# smartbbq.net
KiCad netlist of a schematic drawn in EAGLE
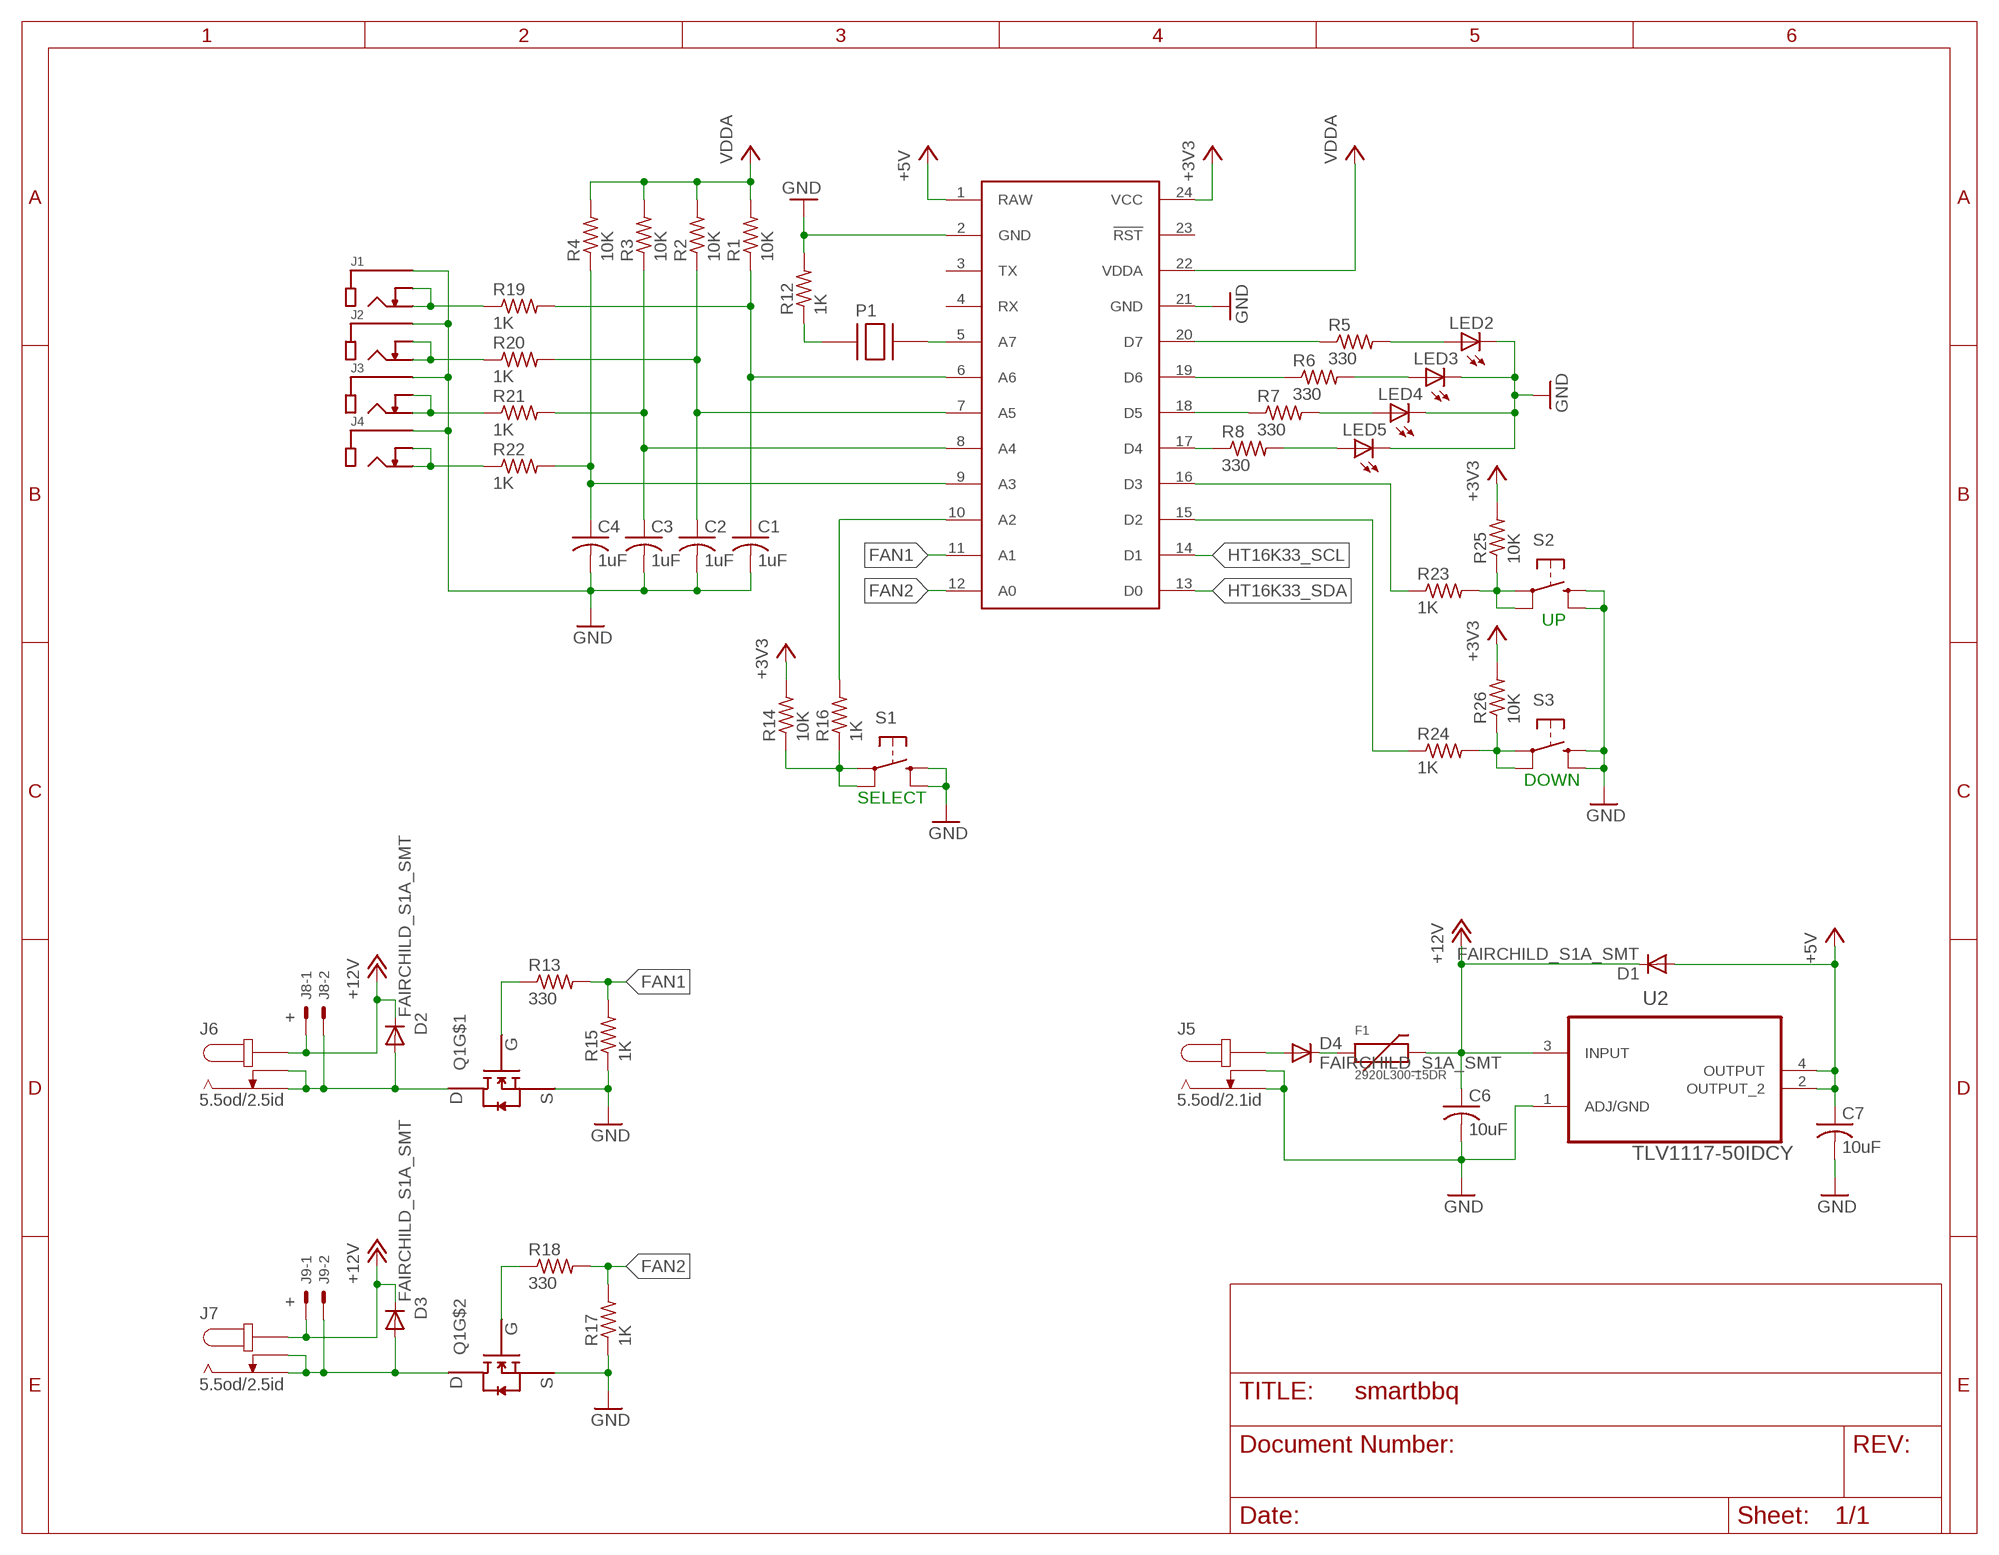
[diagram p0: schematic, sheet 1, part 1 of 2]
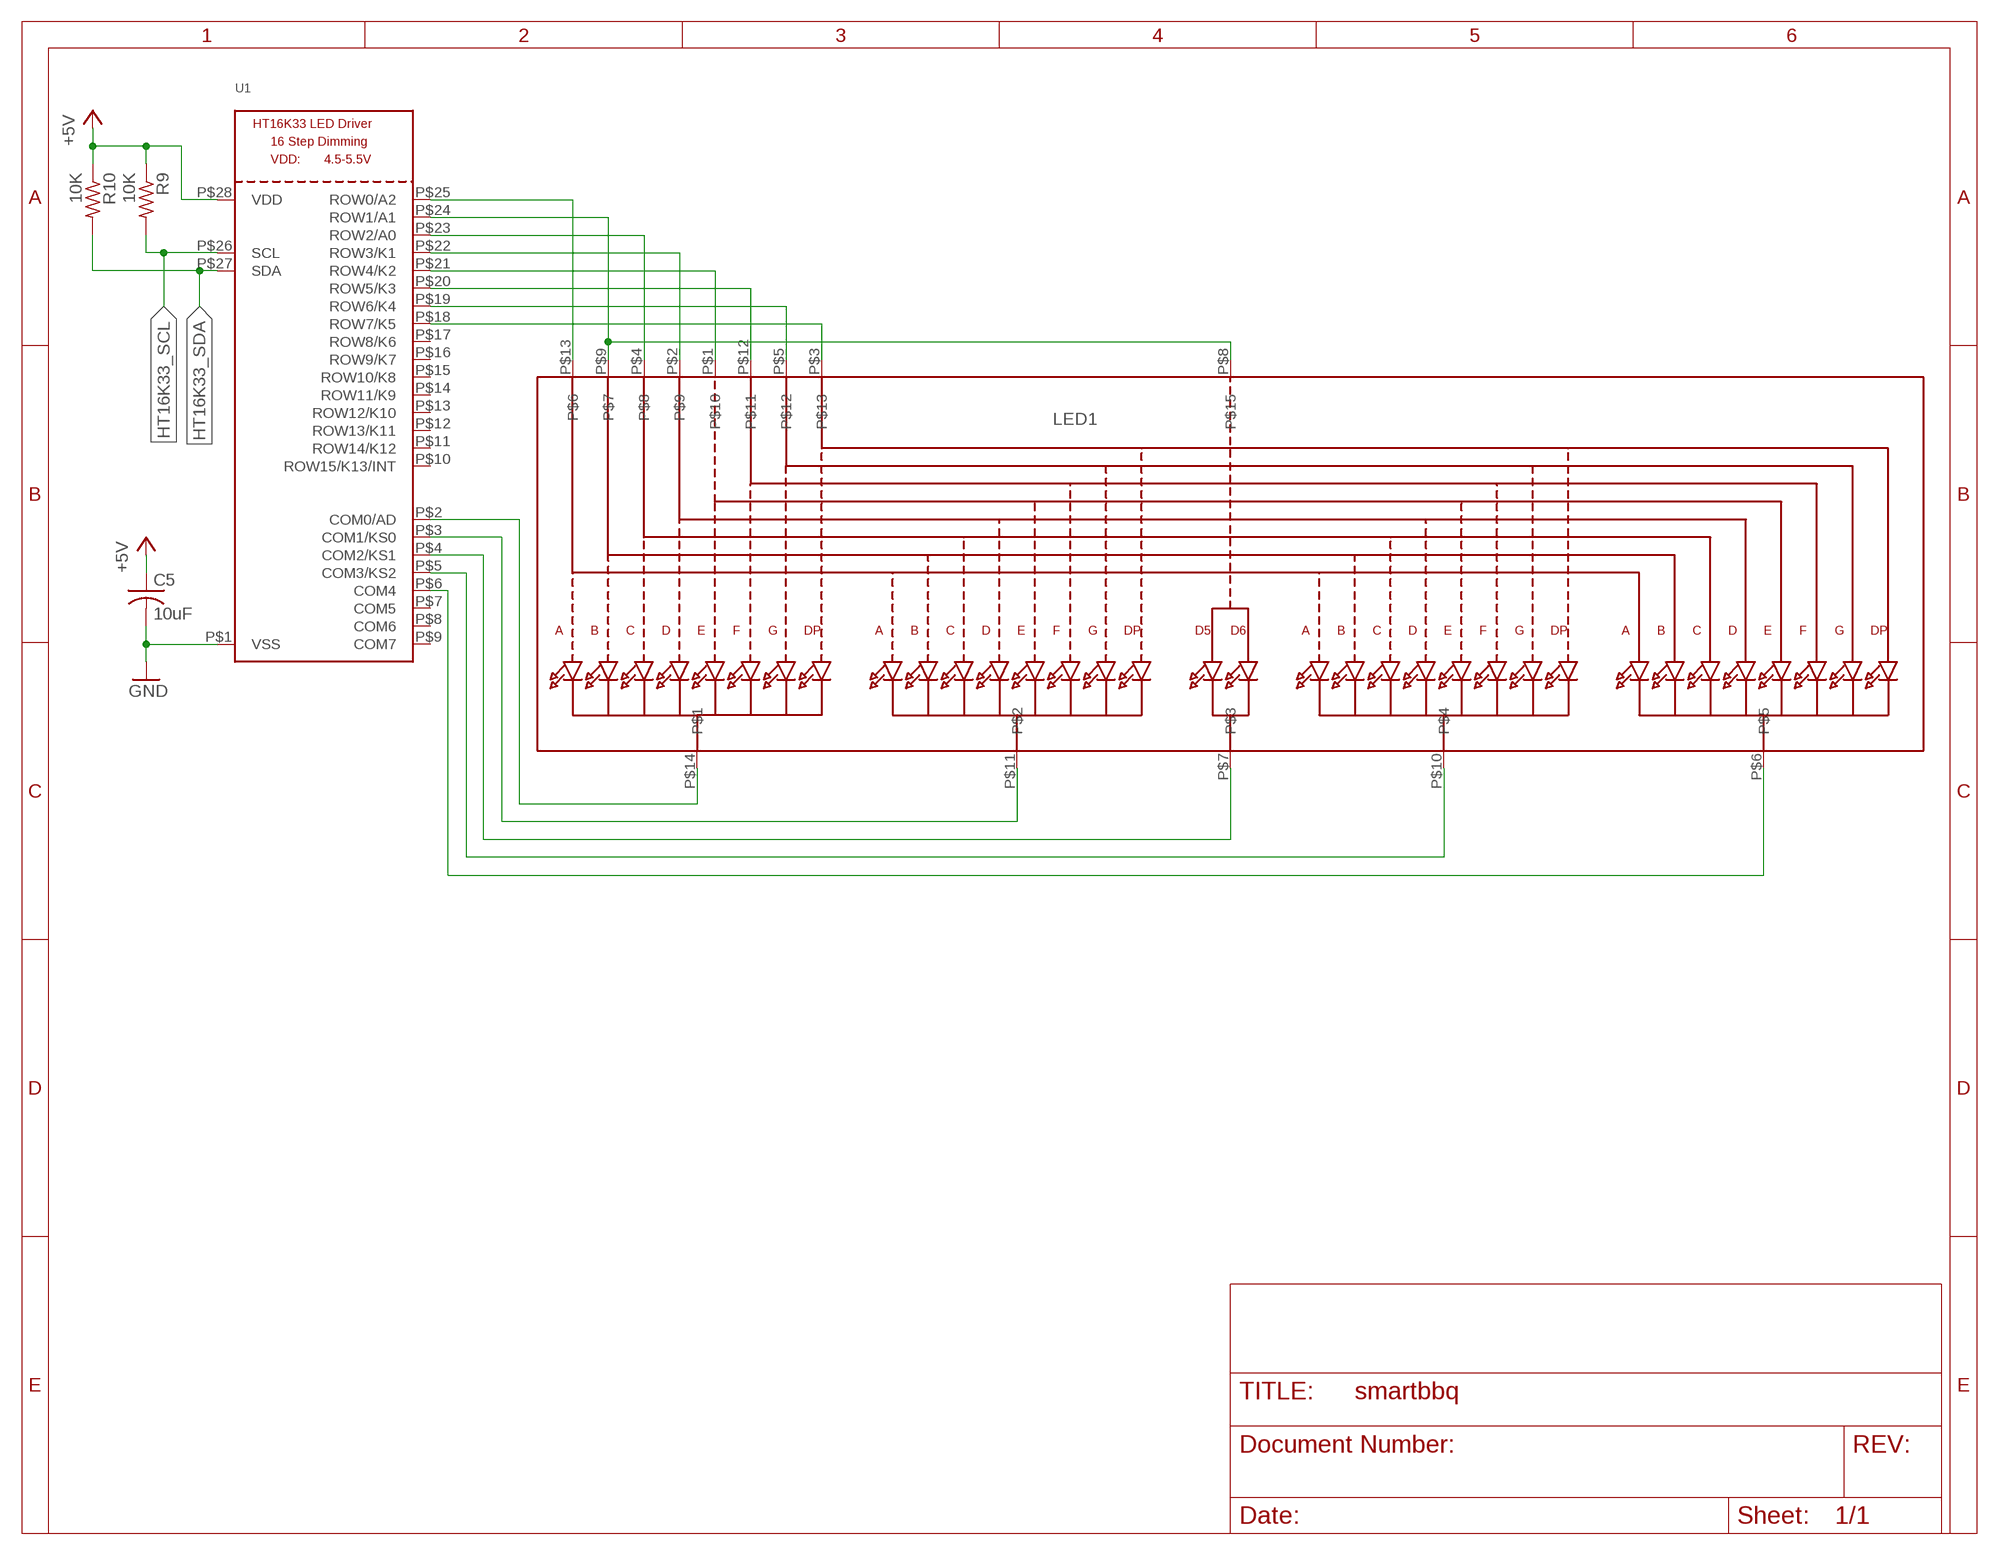
[diagram p1: schematic, sheet 1, part 2 of 2]

(export (version "E")
  (design (tool "Eeschema 10.0.6"))
  (components
    (comp (ref "C1")
      (value "1uF")
      (footprint "eagle-import:C0805")
      (libsource (lib "eagle-import") (part "C-USC0805"))
    )
    (comp (ref "C2")
      (value "1uF")
      (footprint "eagle-import:C0805")
      (libsource (lib "eagle-import") (part "C-USC0805"))
    )
    (comp (ref "C3")
      (value "1uF")
      (footprint "eagle-import:C0805")
      (libsource (lib "eagle-import") (part "C-USC0805"))
    )
    (comp (ref "C4")
      (value "1uF")
      (footprint "eagle-import:C0805")
      (libsource (lib "eagle-import") (part "C-USC0805"))
    )
    (comp (ref "C5")
      (value "10uF")
      (footprint "eagle-import:C0805")
      (libsource (lib "eagle-import") (part "C-USC0805"))
    )
    (comp (ref "C6")
      (value "10uF")
      (footprint "eagle-import:C0805")
      (libsource (lib "eagle-import") (part "C-USC0805"))
    )
    (comp (ref "C7")
      (value "10uF")
      (footprint "eagle-import:C0805")
      (libsource (lib "eagle-import") (part "C-USC0805"))
    )
    (comp (ref "D1")
      (value "FAIRCHILD_S1A_SMT")
      (footprint "eagle-import:FAIRCHILD_S1A_SMT")
      (libsource (lib "eagle-import") (part "FAIRCHILD_S1A_SMT"))
    )
    (comp (ref "D2")
      (value "FAIRCHILD_S1A_SMT")
      (footprint "eagle-import:FAIRCHILD_S1A_SMT")
      (libsource (lib "eagle-import") (part "FAIRCHILD_S1A_SMT"))
    )
    (comp (ref "D3")
      (value "FAIRCHILD_S1A_SMT")
      (footprint "eagle-import:FAIRCHILD_S1A_SMT")
      (libsource (lib "eagle-import") (part "FAIRCHILD_S1A_SMT"))
    )
    (comp (ref "D4")
      (value "FAIRCHILD_S1A_SMT")
      (footprint "eagle-import:FAIRCHILD_S1A_SMT")
      (libsource (lib "eagle-import") (part "FAIRCHILD_S1A_SMT"))
    )
    (comp (ref "F1")
      (value "2920L300-15DR")
      (footprint "eagle-import:2920L300-15DR")
      (libsource (lib "eagle-import") (part "2920L300-15DR"))
    )
    (comp (ref "J1")
      (value "MJ_2523_SMT")
      (footprint "eagle-import:MJ_2523_SMT")
      (libsource (lib "eagle-import") (part "MJ_2523_SMT"))
    )
    (comp (ref "J2")
      (value "MJ_2523_SMT")
      (footprint "eagle-import:MJ_2523_SMT")
      (libsource (lib "eagle-import") (part "MJ_2523_SMT"))
    )
    (comp (ref "J3")
      (value "MJ_2523_SMT")
      (footprint "eagle-import:MJ_2523_SMT")
      (libsource (lib "eagle-import") (part "MJ_2523_SMT"))
    )
    (comp (ref "J4")
      (value "MJ_2523_SMT")
      (footprint "eagle-import:MJ_2523_SMT")
      (libsource (lib "eagle-import") (part "MJ_2523_SMT"))
    )
    (comp (ref "J5")
      (value "5.5od/2.1id")
      (footprint "eagle-import:PJ_002AH_SMT")
      (libsource (lib "eagle-import") (part "PJ_002AH_SMT"))
    )
    (comp (ref "J6")
      (value "5.5od/2.5id")
      (footprint "eagle-import:PJ_002AH_SMT")
      (libsource (lib "eagle-import") (part "PJ_002AH_SMT"))
    )
    (comp (ref "J7")
      (value "5.5od/2.5id")
      (footprint "eagle-import:PJ_002AH_SMT")
      (libsource (lib "eagle-import") (part "PJ_002AH_SMT"))
    )
    (comp (ref "J8")
      (value "+")
      (footprint "eagle-import:7395-02")
      (libsource (lib "eagle-import") (part "22-?-0205-7028"))
    )
    (comp (ref "J9")
      (value "+")
      (footprint "eagle-import:7395-02")
      (libsource (lib "eagle-import") (part "22-?-0205-7028"))
    )
    (comp (ref "LED1")
      (value "DISP_SEGMENT_4DIGIT_BL-Q56C43")
      (footprint "eagle-import:SEGMENT-BL-Q56C43")
      (libsource (lib "eagle-import") (part "DISP_SEGMENT_4DIGIT_BL-Q56C43"))
    )
    (comp (ref "LED2")
      (value "LEDCHIPLED_0805")
      (footprint "eagle-import:CHIPLED_0805")
      (libsource (lib "eagle-import") (part "LEDCHIPLED_0805"))
    )
    (comp (ref "LED3")
      (value "LEDCHIPLED_0805")
      (footprint "eagle-import:CHIPLED_0805")
      (libsource (lib "eagle-import") (part "LEDCHIPLED_0805"))
    )
    (comp (ref "LED4")
      (value "LEDCHIPLED_0805")
      (footprint "eagle-import:CHIPLED_0805")
      (libsource (lib "eagle-import") (part "LEDCHIPLED_0805"))
    )
    (comp (ref "LED5")
      (value "LEDCHIPLED_0805")
      (footprint "eagle-import:CHIPLED_0805")
      (libsource (lib "eagle-import") (part "LEDCHIPLED_0805"))
    )
    (comp (ref "P1")
      (value "CMT_1603_SMT")
      (footprint "eagle-import:CMT_1603_SMT")
      (libsource (lib "eagle-import") (part "CMT_1603_SMT"))
    )
    (comp (ref "Q1")
      (value "SSM6N58NU")
      (footprint "eagle-import:SSM6N58NU")
      (libsource (lib "eagle-import") (part "SSM6N58NU"))
    )
    (comp (ref "R1")
      (value "10K")
      (footprint "eagle-import:R0805")
      (libsource (lib "eagle-import") (part "R-US_R0805"))
    )
    (comp (ref "R2")
      (value "10K")
      (footprint "eagle-import:R0805")
      (libsource (lib "eagle-import") (part "R-US_R0805"))
    )
    (comp (ref "R3")
      (value "10K")
      (footprint "eagle-import:R0805")
      (libsource (lib "eagle-import") (part "R-US_R0805"))
    )
    (comp (ref "R4")
      (value "10K")
      (footprint "eagle-import:R0805")
      (libsource (lib "eagle-import") (part "R-US_R0805"))
    )
    (comp (ref "R5")
      (value "330")
      (footprint "eagle-import:R0805")
      (libsource (lib "eagle-import") (part "R-US_R0805"))
    )
    (comp (ref "R6")
      (value "330")
      (footprint "eagle-import:R0805")
      (libsource (lib "eagle-import") (part "R-US_R0805"))
    )
    (comp (ref "R7")
      (value "330")
      (footprint "eagle-import:R0805")
      (libsource (lib "eagle-import") (part "R-US_R0805"))
    )
    (comp (ref "R8")
      (value "330")
      (footprint "eagle-import:R0805")
      (libsource (lib "eagle-import") (part "R-US_R0805"))
    )
    (comp (ref "R9")
      (value "10K")
      (footprint "eagle-import:R0805")
      (libsource (lib "eagle-import") (part "R-US_R0805"))
    )
    (comp (ref "R10")
      (value "10K")
      (footprint "eagle-import:R0805")
      (libsource (lib "eagle-import") (part "R-US_R0805"))
    )
    (comp (ref "R12")
      (value "1K")
      (footprint "eagle-import:R0805")
      (libsource (lib "eagle-import") (part "R-US_R0805"))
    )
    (comp (ref "R13")
      (value "330")
      (footprint "eagle-import:R0805")
      (libsource (lib "eagle-import") (part "R-US_R0805"))
    )
    (comp (ref "R14")
      (value "10K")
      (footprint "eagle-import:R0805")
      (libsource (lib "eagle-import") (part "R-US_R0805"))
    )
    (comp (ref "R15")
      (value "1K")
      (footprint "eagle-import:R0805")
      (libsource (lib "eagle-import") (part "R-US_R0805"))
    )
    (comp (ref "R16")
      (value "1K")
      (footprint "eagle-import:R0805")
      (libsource (lib "eagle-import") (part "R-US_R0805"))
    )
    (comp (ref "R17")
      (value "1K")
      (footprint "eagle-import:R0805")
      (libsource (lib "eagle-import") (part "R-US_R0805"))
    )
    (comp (ref "R18")
      (value "330")
      (footprint "eagle-import:R0805")
      (libsource (lib "eagle-import") (part "R-US_R0805"))
    )
    (comp (ref "R19")
      (value "1K")
      (footprint "eagle-import:R0805")
      (libsource (lib "eagle-import") (part "R-US_R0805"))
    )
    (comp (ref "R20")
      (value "1K")
      (footprint "eagle-import:R0805")
      (libsource (lib "eagle-import") (part "R-US_R0805"))
    )
    (comp (ref "R21")
      (value "1K")
      (footprint "eagle-import:R0805")
      (libsource (lib "eagle-import") (part "R-US_R0805"))
    )
    (comp (ref "R22")
      (value "1K")
      (footprint "eagle-import:R0805")
      (libsource (lib "eagle-import") (part "R-US_R0805"))
    )
    (comp (ref "R23")
      (value "1K")
      (footprint "eagle-import:R0805")
      (libsource (lib "eagle-import") (part "R-US_R0805"))
    )
    (comp (ref "R24")
      (value "1K")
      (footprint "eagle-import:R0805")
      (libsource (lib "eagle-import") (part "R-US_R0805"))
    )
    (comp (ref "R25")
      (value "10K")
      (footprint "eagle-import:R0805")
      (libsource (lib "eagle-import") (part "R-US_R0805"))
    )
    (comp (ref "R26")
      (value "10K")
      (footprint "eagle-import:R0805")
      (libsource (lib "eagle-import") (part "R-US_R0805"))
    )
    (comp (ref "S1")
      (value "PANASONIC-EVQ")
      (footprint "eagle-import:PANASONIC-EVQ")
      (libsource (lib "eagle-import") (part "PANASONIC-EVQ"))
    )
    (comp (ref "S2")
      (value "PANASONIC-EVQ")
      (footprint "eagle-import:PANASONIC-EVQ")
      (libsource (lib "eagle-import") (part "PANASONIC-EVQ"))
    )
    (comp (ref "S3")
      (value "PANASONIC-EVQ")
      (footprint "eagle-import:PANASONIC-EVQ")
      (libsource (lib "eagle-import") (part "PANASONIC-EVQ"))
    )
    (comp (ref "SPARK")
      (value "SPARK_CORECORE")
      (footprint "eagle-import:SPARK_CORE")
      (libsource (lib "eagle-import") (part "SPARK_CORECORE"))
    )
    (comp (ref "U1")
      (value "HT16K33_SOP28")
      (footprint "eagle-import:SOP28_300MIL")
      (libsource (lib "eagle-import") (part "HT16K33_SOP28"))
    )
    (comp (ref "U2")
      (value "TLV1117-50IDCY")
      (footprint "eagle-import:SOT230P700X180-4N")
      (fields (field (name "MPN") "TLV1117-33IDCY"))
      (libsource (lib "eagle-import") (part "TLV1117-33IDCY"))
    )
  )
  (nets
    (net (code "1") (name "+3V3") (class "Default")
      (node (ref "R14") (pin "2") (pinfunction "2_2") (pintype "passive"))
      (node (ref "R25") (pin "2") (pinfunction "2_2") (pintype "passive"))
      (node (ref "R26") (pin "2") (pinfunction "2_2") (pintype "passive"))
      (node (ref "SPARK") (pin "24") (pinfunction "VCC_24") (pintype "power_in"))
    )
    (net (code "2") (name "+5V") (class "Default")
      (node (ref "C5") (pin "1") (pinfunction "1_1") (pintype "passive"))
      (node (ref "C7") (pin "1") (pinfunction "1_1") (pintype "passive"))
      (node (ref "D1") (pin "P$1") (pinfunction "A_P$1") (pintype "passive"))
      (node (ref "R10") (pin "1") (pinfunction "1_1") (pintype "passive"))
      (node (ref "R9") (pin "1") (pinfunction "1_1") (pintype "passive"))
      (node (ref "SPARK") (pin "1") (pinfunction "RAW_1") (pintype "power_in"))
      (node (ref "U1") (pin "P$28") (pinfunction "VDD_P$28") (pintype "bidirectional"))
      (node (ref "U2") (pin "2") (pinfunction "OUTPUT_2_2") (pintype "output"))
      (node (ref "U2") (pin "4") (pinfunction "OUTPUT_4") (pintype "output"))
    )
    (net (code "3") (name "+12V") (class "Default")
      (node (ref "C6") (pin "1") (pinfunction "1_1") (pintype "passive"))
      (node (ref "D1") (pin "P$2") (pinfunction "C_P$2") (pintype "passive"))
      (node (ref "D2") (pin "P$2") (pinfunction "C_P$2") (pintype "passive"))
      (node (ref "D3") (pin "P$2") (pinfunction "C_P$2") (pintype "passive"))
      (node (ref "F1") (pin "P$2") (pinfunction "P$2_P$2") (pintype "passive"))
      (node (ref "J6") (pin "P$1") (pinfunction "P$1_P$1") (pintype "passive"))
      (node (ref "J6") (pin "P$4") (pinfunction "P$1_P$4") (pintype "passive"))
      (node (ref "J7") (pin "P$1") (pinfunction "P$1_P$1") (pintype "passive"))
      (node (ref "J7") (pin "P$4") (pinfunction "P$1_P$4") (pintype "passive"))
      (node (ref "J8") (pin "1") (pinfunction "S_1") (pintype "passive"))
      (node (ref "J9") (pin "1") (pinfunction "S_1") (pintype "passive"))
      (node (ref "U2") (pin "3") (pinfunction "INPUT_3") (pintype "input"))
    )
    (net (code "4") (name "FAN1") (class "Default")
      (node (ref "R13") (pin "2") (pinfunction "2_2") (pintype "passive"))
      (node (ref "R15") (pin "2") (pinfunction "2_2") (pintype "passive"))
      (node (ref "SPARK") (pin "11") (pinfunction "A1_11") (pintype "bidirectional"))
    )
    (net (code "5") (name "FAN2") (class "Default")
      (node (ref "R17") (pin "2") (pinfunction "2_2") (pintype "passive"))
      (node (ref "R18") (pin "2") (pinfunction "2_2") (pintype "passive"))
      (node (ref "SPARK") (pin "12") (pinfunction "A0_12") (pintype "bidirectional"))
    )
    (net (code "6") (name "GND") (class "Default")
      (node (ref "C1") (pin "2") (pinfunction "2_2") (pintype "passive"))
      (node (ref "C2") (pin "2") (pinfunction "2_2") (pintype "passive"))
      (node (ref "C3") (pin "2") (pinfunction "2_2") (pintype "passive"))
      (node (ref "C4") (pin "2") (pinfunction "2_2") (pintype "passive"))
      (node (ref "C5") (pin "2") (pinfunction "2_2") (pintype "passive"))
      (node (ref "C6") (pin "2") (pinfunction "2_2") (pintype "passive"))
      (node (ref "C7") (pin "2") (pinfunction "2_2") (pintype "passive"))
      (node (ref "J1") (pin "P$1") (pinfunction "P$1_P$1") (pintype "bidirectional"))
      (node (ref "J2") (pin "P$1") (pinfunction "P$1_P$1") (pintype "bidirectional"))
      (node (ref "J3") (pin "P$1") (pinfunction "P$1_P$1") (pintype "bidirectional"))
      (node (ref "J4") (pin "P$1") (pinfunction "P$1_P$1") (pintype "bidirectional"))
      (node (ref "J5") (pin "P$2") (pinfunction "P$2_P$2") (pintype "passive"))
      (node (ref "J5") (pin "P$3") (pinfunction "P$3_P$3") (pintype "passive"))
      (node (ref "LED2") (pin "C") (pinfunction "C_C") (pintype "passive"))
      (node (ref "LED3") (pin "C") (pinfunction "C_C") (pintype "passive"))
      (node (ref "LED4") (pin "C") (pinfunction "C_C") (pintype "passive"))
      (node (ref "LED5") (pin "C") (pinfunction "C_C") (pintype "passive"))
      (node (ref "Q1") (pin "P$1") (pinfunction "P$1_P$1") (pintype "passive"))
      (node (ref "Q1") (pin "P$4") (pinfunction "P$1_P$4") (pintype "passive"))
      (node (ref "R12") (pin "2") (pinfunction "2_2") (pintype "passive"))
      (node (ref "R15") (pin "1") (pinfunction "1_1") (pintype "passive"))
      (node (ref "R17") (pin "1") (pinfunction "1_1") (pintype "passive"))
      (node (ref "S1") (pin "P$3") (pinfunction "3_P$3") (pintype "passive"))
      (node (ref "S1") (pin "P$4") (pinfunction "4_P$4") (pintype "passive"))
      (node (ref "S2") (pin "P$3") (pinfunction "3_P$3") (pintype "passive"))
      (node (ref "S2") (pin "P$4") (pinfunction "4_P$4") (pintype "passive"))
      (node (ref "S3") (pin "P$3") (pinfunction "3_P$3") (pintype "passive"))
      (node (ref "S3") (pin "P$4") (pinfunction "4_P$4") (pintype "passive"))
      (node (ref "SPARK") (pin "2") (pinfunction "GND_2") (pintype "power_in"))
      (node (ref "SPARK") (pin "21") (pinfunction "GND_21") (pintype "power_in"))
      (node (ref "U1") (pin "P$1") (pinfunction "VSS_P$1") (pintype "bidirectional"))
      (node (ref "U2") (pin "1") (pinfunction "ADJ/GND_1") (pintype "input"))
    )
    (net (code "7") (name "HT16K33_SCL") (class "Default")
      (node (ref "R9") (pin "2") (pinfunction "2_2") (pintype "passive"))
      (node (ref "SPARK") (pin "14") (pinfunction "D1_14") (pintype "bidirectional"))
      (node (ref "U1") (pin "P$26") (pinfunction "SCL_P$26") (pintype "bidirectional"))
    )
    (net (code "8") (name "HT16K33_SDA") (class "Default")
      (node (ref "R10") (pin "2") (pinfunction "2_2") (pintype "passive"))
      (node (ref "SPARK") (pin "13") (pinfunction "D0_13") (pintype "bidirectional"))
      (node (ref "U1") (pin "P$27") (pinfunction "SDA_P$27") (pintype "bidirectional"))
    )
    (net (code "9") (name "Net-(D2-A)") (class "Default")
      (node (ref "D2") (pin "P$1") (pinfunction "A_P$1") (pintype "passive"))
      (node (ref "J6") (pin "P$2") (pinfunction "P$2_P$2") (pintype "passive"))
      (node (ref "J6") (pin "P$3") (pinfunction "P$3_P$3") (pintype "passive"))
      (node (ref "J8") (pin "2") (pinfunction "S_2") (pintype "passive"))
      (node (ref "Q1") (pin "P$6") (pinfunction "P$3_P$6") (pintype "passive"))
    )
    (net (code "10") (name "Net-(D3-A)") (class "Default")
      (node (ref "D3") (pin "P$1") (pinfunction "A_P$1") (pintype "passive"))
      (node (ref "J7") (pin "P$2") (pinfunction "P$2_P$2") (pintype "passive"))
      (node (ref "J7") (pin "P$3") (pinfunction "P$3_P$3") (pintype "passive"))
      (node (ref "J9") (pin "2") (pinfunction "S_2") (pintype "passive"))
      (node (ref "Q1") (pin "P$3") (pinfunction "P$3_P$3") (pintype "passive"))
    )
    (net (code "11") (name "Net-(D4-A)") (class "Default")
      (node (ref "D4") (pin "P$1") (pinfunction "A_P$1") (pintype "passive"))
      (node (ref "J5") (pin "P$1") (pinfunction "P$1_P$1") (pintype "passive"))
      (node (ref "J5") (pin "P$4") (pinfunction "P$1_P$4") (pintype "passive"))
    )
    (net (code "12") (name "Net-(D4-C)") (class "Default")
      (node (ref "D4") (pin "P$2") (pinfunction "C_P$2") (pintype "passive"))
      (node (ref "F1") (pin "P$1") (pinfunction "P$1_P$1") (pintype "passive"))
    )
    (net (code "13") (name "Net-(J1-PadP$2)") (class "Default")
      (node (ref "J1") (pin "P$2") (pinfunction "P$2_P$2") (pintype "bidirectional"))
      (node (ref "J1") (pin "P$3") (pinfunction "P$3_P$3") (pintype "bidirectional"))
      (node (ref "R19") (pin "1") (pinfunction "1_1") (pintype "passive"))
    )
    (net (code "14") (name "Net-(J2-PadP$2)") (class "Default")
      (node (ref "J2") (pin "P$2") (pinfunction "P$2_P$2") (pintype "bidirectional"))
      (node (ref "J2") (pin "P$3") (pinfunction "P$3_P$3") (pintype "bidirectional"))
      (node (ref "R20") (pin "1") (pinfunction "1_1") (pintype "passive"))
    )
    (net (code "15") (name "Net-(J3-PadP$2)") (class "Default")
      (node (ref "J3") (pin "P$2") (pinfunction "P$2_P$2") (pintype "bidirectional"))
      (node (ref "J3") (pin "P$3") (pinfunction "P$3_P$3") (pintype "bidirectional"))
      (node (ref "R21") (pin "1") (pinfunction "1_1") (pintype "passive"))
    )
    (net (code "16") (name "Net-(J4-PadP$2)") (class "Default")
      (node (ref "J4") (pin "P$2") (pinfunction "P$2_P$2") (pintype "bidirectional"))
      (node (ref "J4") (pin "P$3") (pinfunction "P$3_P$3") (pintype "bidirectional"))
      (node (ref "R22") (pin "1") (pinfunction "1_1") (pintype "passive"))
    )
    (net (code "17") (name "Net-(LED1-P$1)") (class "Default")
      (node (ref "LED1") (pin "P$14") (pinfunction "P$1_P$14") (pintype "bidirectional"))
      (node (ref "U1") (pin "P$2") (pinfunction "COM0/AD_P$2") (pintype "bidirectional"))
    )
    (net (code "18") (name "Net-(LED1-P$2)") (class "Default")
      (node (ref "LED1") (pin "P$11") (pinfunction "P$2_P$11") (pintype "bidirectional"))
      (node (ref "U1") (pin "P$3") (pinfunction "COM1/KS0_P$3") (pintype "bidirectional"))
    )
    (net (code "19") (name "Net-(LED1-P$3)") (class "Default")
      (node (ref "LED1") (pin "P$7") (pinfunction "P$3_P$7") (pintype "bidirectional"))
      (node (ref "U1") (pin "P$4") (pinfunction "COM2/KS1_P$4") (pintype "bidirectional"))
    )
    (net (code "20") (name "Net-(LED1-P$4)") (class "Default")
      (node (ref "LED1") (pin "P$10") (pinfunction "P$4_P$10") (pintype "bidirectional"))
      (node (ref "U1") (pin "P$5") (pinfunction "COM3/KS2_P$5") (pintype "bidirectional"))
    )
    (net (code "21") (name "Net-(LED1-P$5)") (class "Default")
      (node (ref "LED1") (pin "P$6") (pinfunction "P$5_P$6") (pintype "bidirectional"))
      (node (ref "U1") (pin "P$6") (pinfunction "COM4_P$6") (pintype "bidirectional"))
    )
    (net (code "22") (name "Net-(LED1-P$6)") (class "Default")
      (node (ref "LED1") (pin "P$13") (pinfunction "P$6_P$13") (pintype "bidirectional"))
      (node (ref "U1") (pin "P$25") (pinfunction "ROW0/A2_P$25") (pintype "bidirectional"))
    )
    (net (code "23") (name "Net-(LED1-P$8)") (class "Default")
      (node (ref "LED1") (pin "P$4") (pinfunction "P$8_P$4") (pintype "bidirectional"))
      (node (ref "U1") (pin "P$23") (pinfunction "ROW2/A0_P$23") (pintype "bidirectional"))
    )
    (net (code "24") (name "Net-(LED1-P$9)") (class "Default")
      (node (ref "LED1") (pin "P$2") (pinfunction "P$9_P$2") (pintype "bidirectional"))
      (node (ref "U1") (pin "P$22") (pinfunction "ROW3/K1_P$22") (pintype "bidirectional"))
    )
    (net (code "25") (name "Net-(LED1-P$10)") (class "Default")
      (node (ref "LED1") (pin "P$1") (pinfunction "P$10_P$1") (pintype "bidirectional"))
      (node (ref "U1") (pin "P$21") (pinfunction "ROW4/K2_P$21") (pintype "bidirectional"))
    )
    (net (code "26") (name "Net-(LED1-P$11)") (class "Default")
      (node (ref "LED1") (pin "P$12") (pinfunction "P$11_P$12") (pintype "bidirectional"))
      (node (ref "U1") (pin "P$20") (pinfunction "ROW5/K3_P$20") (pintype "bidirectional"))
    )
    (net (code "27") (name "Net-(LED1-P$12)") (class "Default")
      (node (ref "LED1") (pin "P$5") (pinfunction "P$12_P$5") (pintype "bidirectional"))
      (node (ref "U1") (pin "P$19") (pinfunction "ROW6/K4_P$19") (pintype "bidirectional"))
    )
    (net (code "28") (name "Net-(LED1-P$13)") (class "Default")
      (node (ref "LED1") (pin "P$3") (pinfunction "P$13_P$3") (pintype "bidirectional"))
      (node (ref "U1") (pin "P$18") (pinfunction "ROW7/K5_P$18") (pintype "bidirectional"))
    )
    (net (code "29") (name "Net-(LED1-P$15)") (class "Default")
      (node (ref "LED1") (pin "P$8") (pinfunction "P$15_P$8") (pintype "bidirectional"))
      (node (ref "LED1") (pin "P$9") (pinfunction "P$7_P$9") (pintype "bidirectional"))
      (node (ref "U1") (pin "P$24") (pinfunction "ROW1/A1_P$24") (pintype "bidirectional"))
    )
    (net (code "30") (name "Net-(LED2-PadA)") (class "Default")
      (node (ref "LED2") (pin "A") (pinfunction "A_A") (pintype "passive"))
      (node (ref "R5") (pin "2") (pinfunction "2_2") (pintype "passive"))
    )
    (net (code "31") (name "Net-(LED3-PadA)") (class "Default")
      (node (ref "LED3") (pin "A") (pinfunction "A_A") (pintype "passive"))
      (node (ref "R6") (pin "2") (pinfunction "2_2") (pintype "passive"))
    )
    (net (code "32") (name "Net-(LED4-PadA)") (class "Default")
      (node (ref "LED4") (pin "A") (pinfunction "A_A") (pintype "passive"))
      (node (ref "R7") (pin "2") (pinfunction "2_2") (pintype "passive"))
    )
    (net (code "33") (name "Net-(LED5-PadA)") (class "Default")
      (node (ref "LED5") (pin "A") (pinfunction "A_A") (pintype "passive"))
      (node (ref "R8") (pin "2") (pinfunction "2_2") (pintype "passive"))
    )
    (net (code "34") (name "Net-(P1-PadP$1)") (class "Default")
      (node (ref "P1") (pin "P$1") (pinfunction "P$1_P$1") (pintype "bidirectional"))
      (node (ref "R12") (pin "1") (pinfunction "1_1") (pintype "passive"))
    )
    (net (code "35") (name "Net-(Q1-PadP$2)") (class "Default")
      (node (ref "Q1") (pin "P$2") (pinfunction "P$2_P$2") (pintype "passive"))
      (node (ref "R13") (pin "1") (pinfunction "1_1") (pintype "passive"))
    )
    (net (code "36") (name "Net-(Q1B-P$2)") (class "Default")
      (node (ref "Q1") (pin "P$5") (pinfunction "P$2_P$5") (pintype "passive"))
      (node (ref "R18") (pin "1") (pinfunction "1_1") (pintype "passive"))
    )
    (net (code "37") (name "Net-(S1-1)") (class "Default")
      (node (ref "R14") (pin "1") (pinfunction "1_1") (pintype "passive"))
      (node (ref "R16") (pin "1") (pinfunction "1_1") (pintype "passive"))
      (node (ref "S1") (pin "P$1") (pinfunction "1_P$1") (pintype "passive"))
      (node (ref "S1") (pin "P$2") (pinfunction "2_P$2") (pintype "passive"))
    )
    (net (code "38") (name "Net-(S2-1)") (class "Default")
      (node (ref "R23") (pin "2") (pinfunction "2_2") (pintype "passive"))
      (node (ref "R25") (pin "1") (pinfunction "1_1") (pintype "passive"))
      (node (ref "S2") (pin "P$1") (pinfunction "1_P$1") (pintype "passive"))
      (node (ref "S2") (pin "P$2") (pinfunction "2_P$2") (pintype "passive"))
    )
    (net (code "39") (name "Net-(S3-1)") (class "Default")
      (node (ref "R24") (pin "2") (pinfunction "2_2") (pintype "passive"))
      (node (ref "R26") (pin "1") (pinfunction "1_1") (pintype "passive"))
      (node (ref "S3") (pin "P$1") (pinfunction "1_P$1") (pintype "passive"))
      (node (ref "S3") (pin "P$2") (pinfunction "2_P$2") (pintype "passive"))
    )
    (net (code "40") (name "Net-(SPARK-A2)") (class "Default")
      (node (ref "R16") (pin "2") (pinfunction "2_2") (pintype "passive"))
      (node (ref "SPARK") (pin "10") (pinfunction "A2_10") (pintype "bidirectional"))
    )
    (net (code "41") (name "Net-(SPARK-A3)") (class "Default")
      (node (ref "C4") (pin "1") (pinfunction "1_1") (pintype "passive"))
      (node (ref "R22") (pin "2") (pinfunction "2_2") (pintype "passive"))
      (node (ref "R4") (pin "1") (pinfunction "1_1") (pintype "passive"))
      (node (ref "SPARK") (pin "9") (pinfunction "A3_9") (pintype "bidirectional"))
    )
    (net (code "42") (name "Net-(SPARK-A4)") (class "Default")
      (node (ref "C3") (pin "1") (pinfunction "1_1") (pintype "passive"))
      (node (ref "R21") (pin "2") (pinfunction "2_2") (pintype "passive"))
      (node (ref "R3") (pin "1") (pinfunction "1_1") (pintype "passive"))
      (node (ref "SPARK") (pin "8") (pinfunction "A4_8") (pintype "bidirectional"))
    )
    (net (code "43") (name "Net-(SPARK-A5)") (class "Default")
      (node (ref "C2") (pin "1") (pinfunction "1_1") (pintype "passive"))
      (node (ref "R2") (pin "1") (pinfunction "1_1") (pintype "passive"))
      (node (ref "R20") (pin "2") (pinfunction "2_2") (pintype "passive"))
      (node (ref "SPARK") (pin "7") (pinfunction "A5_7") (pintype "bidirectional"))
    )
    (net (code "44") (name "Net-(SPARK-A6)") (class "Default")
      (node (ref "C1") (pin "1") (pinfunction "1_1") (pintype "passive"))
      (node (ref "R1") (pin "1") (pinfunction "1_1") (pintype "passive"))
      (node (ref "R19") (pin "2") (pinfunction "2_2") (pintype "passive"))
      (node (ref "SPARK") (pin "6") (pinfunction "A6_6") (pintype "bidirectional"))
    )
    (net (code "45") (name "Net-(SPARK-A7)") (class "Default")
      (node (ref "P1") (pin "P$2") (pinfunction "P$2_P$2") (pintype "bidirectional"))
      (node (ref "SPARK") (pin "5") (pinfunction "A7_5") (pintype "bidirectional"))
    )
    (net (code "46") (name "Net-(SPARK-D2)") (class "Default")
      (node (ref "R24") (pin "1") (pinfunction "1_1") (pintype "passive"))
      (node (ref "SPARK") (pin "15") (pinfunction "D2_15") (pintype "bidirectional"))
    )
    (net (code "47") (name "Net-(SPARK-D3)") (class "Default")
      (node (ref "R23") (pin "1") (pinfunction "1_1") (pintype "passive"))
      (node (ref "SPARK") (pin "16") (pinfunction "D3_16") (pintype "bidirectional"))
    )
    (net (code "48") (name "Net-(SPARK-D4)") (class "Default")
      (node (ref "R8") (pin "1") (pinfunction "1_1") (pintype "passive"))
      (node (ref "SPARK") (pin "17") (pinfunction "D4_17") (pintype "bidirectional"))
    )
    (net (code "49") (name "Net-(SPARK-D5)") (class "Default")
      (node (ref "R7") (pin "1") (pinfunction "1_1") (pintype "passive"))
      (node (ref "SPARK") (pin "18") (pinfunction "D5_18") (pintype "bidirectional"))
    )
    (net (code "50") (name "Net-(SPARK-D6)") (class "Default")
      (node (ref "R6") (pin "1") (pinfunction "1_1") (pintype "passive"))
      (node (ref "SPARK") (pin "19") (pinfunction "D6_19") (pintype "bidirectional"))
    )
    (net (code "51") (name "Net-(SPARK-D7)") (class "Default")
      (node (ref "R5") (pin "1") (pinfunction "1_1") (pintype "passive"))
      (node (ref "SPARK") (pin "20") (pinfunction "D7_20") (pintype "bidirectional"))
    )
    (net (code "52") (name "VDDA") (class "Default")
      (node (ref "R1") (pin "2") (pinfunction "2_2") (pintype "passive"))
      (node (ref "R2") (pin "2") (pinfunction "2_2") (pintype "passive"))
      (node (ref "R3") (pin "2") (pinfunction "2_2") (pintype "passive"))
      (node (ref "R4") (pin "2") (pinfunction "2_2") (pintype "passive"))
      (node (ref "SPARK") (pin "22") (pinfunction "VDDA_22") (pintype "power_in"))
    )
    (net (code "53") (name "unconnected-(SPARK-RX-Pad4)") (class "Default")
      (node (ref "SPARK") (pin "4") (pinfunction "RX_4") (pintype "bidirectional"))
    )
    (net (code "54") (name "unconnected-(SPARK-TX-Pad3)") (class "Default")
      (node (ref "SPARK") (pin "3") (pinfunction "TX_3") (pintype "bidirectional"))
    )
    (net (code "55") (name "unconnected-(SPARK-~{RST}-Pad23)") (class "Default")
      (node (ref "SPARK") (pin "23") (pinfunction "~{RST}_23") (pintype "bidirectional"))
    )
    (net (code "56") (name "unconnected-(U1-COM5-PadP$7)") (class "Default")
      (node (ref "U1") (pin "P$7") (pinfunction "COM5_P$7") (pintype "bidirectional"))
    )
    (net (code "57") (name "unconnected-(U1-COM6-PadP$8)") (class "Default")
      (node (ref "U1") (pin "P$8") (pinfunction "COM6_P$8") (pintype "bidirectional"))
    )
    (net (code "58") (name "unconnected-(U1-COM7-PadP$9)") (class "Default")
      (node (ref "U1") (pin "P$9") (pinfunction "COM7_P$9") (pintype "bidirectional"))
    )
    (net (code "59") (name "unconnected-(U1-ROW8{slash}K6-PadP$17)") (class "Default")
      (node (ref "U1") (pin "P$17") (pinfunction "ROW8/K6_P$17") (pintype "bidirectional"))
    )
    (net (code "60") (name "unconnected-(U1-ROW9{slash}K7-PadP$16)") (class "Default")
      (node (ref "U1") (pin "P$16") (pinfunction "ROW9/K7_P$16") (pintype "bidirectional"))
    )
    (net (code "61") (name "unconnected-(U1-ROW10{slash}K8-PadP$15)") (class "Default")
      (node (ref "U1") (pin "P$15") (pinfunction "ROW10/K8_P$15") (pintype "bidirectional"))
    )
    (net (code "62") (name "unconnected-(U1-ROW11{slash}K9-PadP$14)") (class "Default")
      (node (ref "U1") (pin "P$14") (pinfunction "ROW11/K9_P$14") (pintype "bidirectional"))
    )
    (net (code "63") (name "unconnected-(U1-ROW12{slash}K10-PadP$13)") (class "Default")
      (node (ref "U1") (pin "P$13") (pinfunction "ROW12/K10_P$13") (pintype "bidirectional"))
    )
    (net (code "64") (name "unconnected-(U1-ROW13{slash}K11-PadP$12)") (class "Default")
      (node (ref "U1") (pin "P$12") (pinfunction "ROW13/K11_P$12") (pintype "bidirectional"))
    )
    (net (code "65") (name "unconnected-(U1-ROW14{slash}K12-PadP$11)") (class "Default")
      (node (ref "U1") (pin "P$11") (pinfunction "ROW14/K12_P$11") (pintype "bidirectional"))
    )
    (net (code "66") (name "unconnected-(U1-ROW15{slash}K13{slash}INT-PadP$10)") (class "Default")
      (node (ref "U1") (pin "P$10") (pinfunction "ROW15/K13/INT_P$10") (pintype "bidirectional"))
    )
  )
)
